# logic_pirate.net
KiCad netlist of a schematic drawn in EAGLE
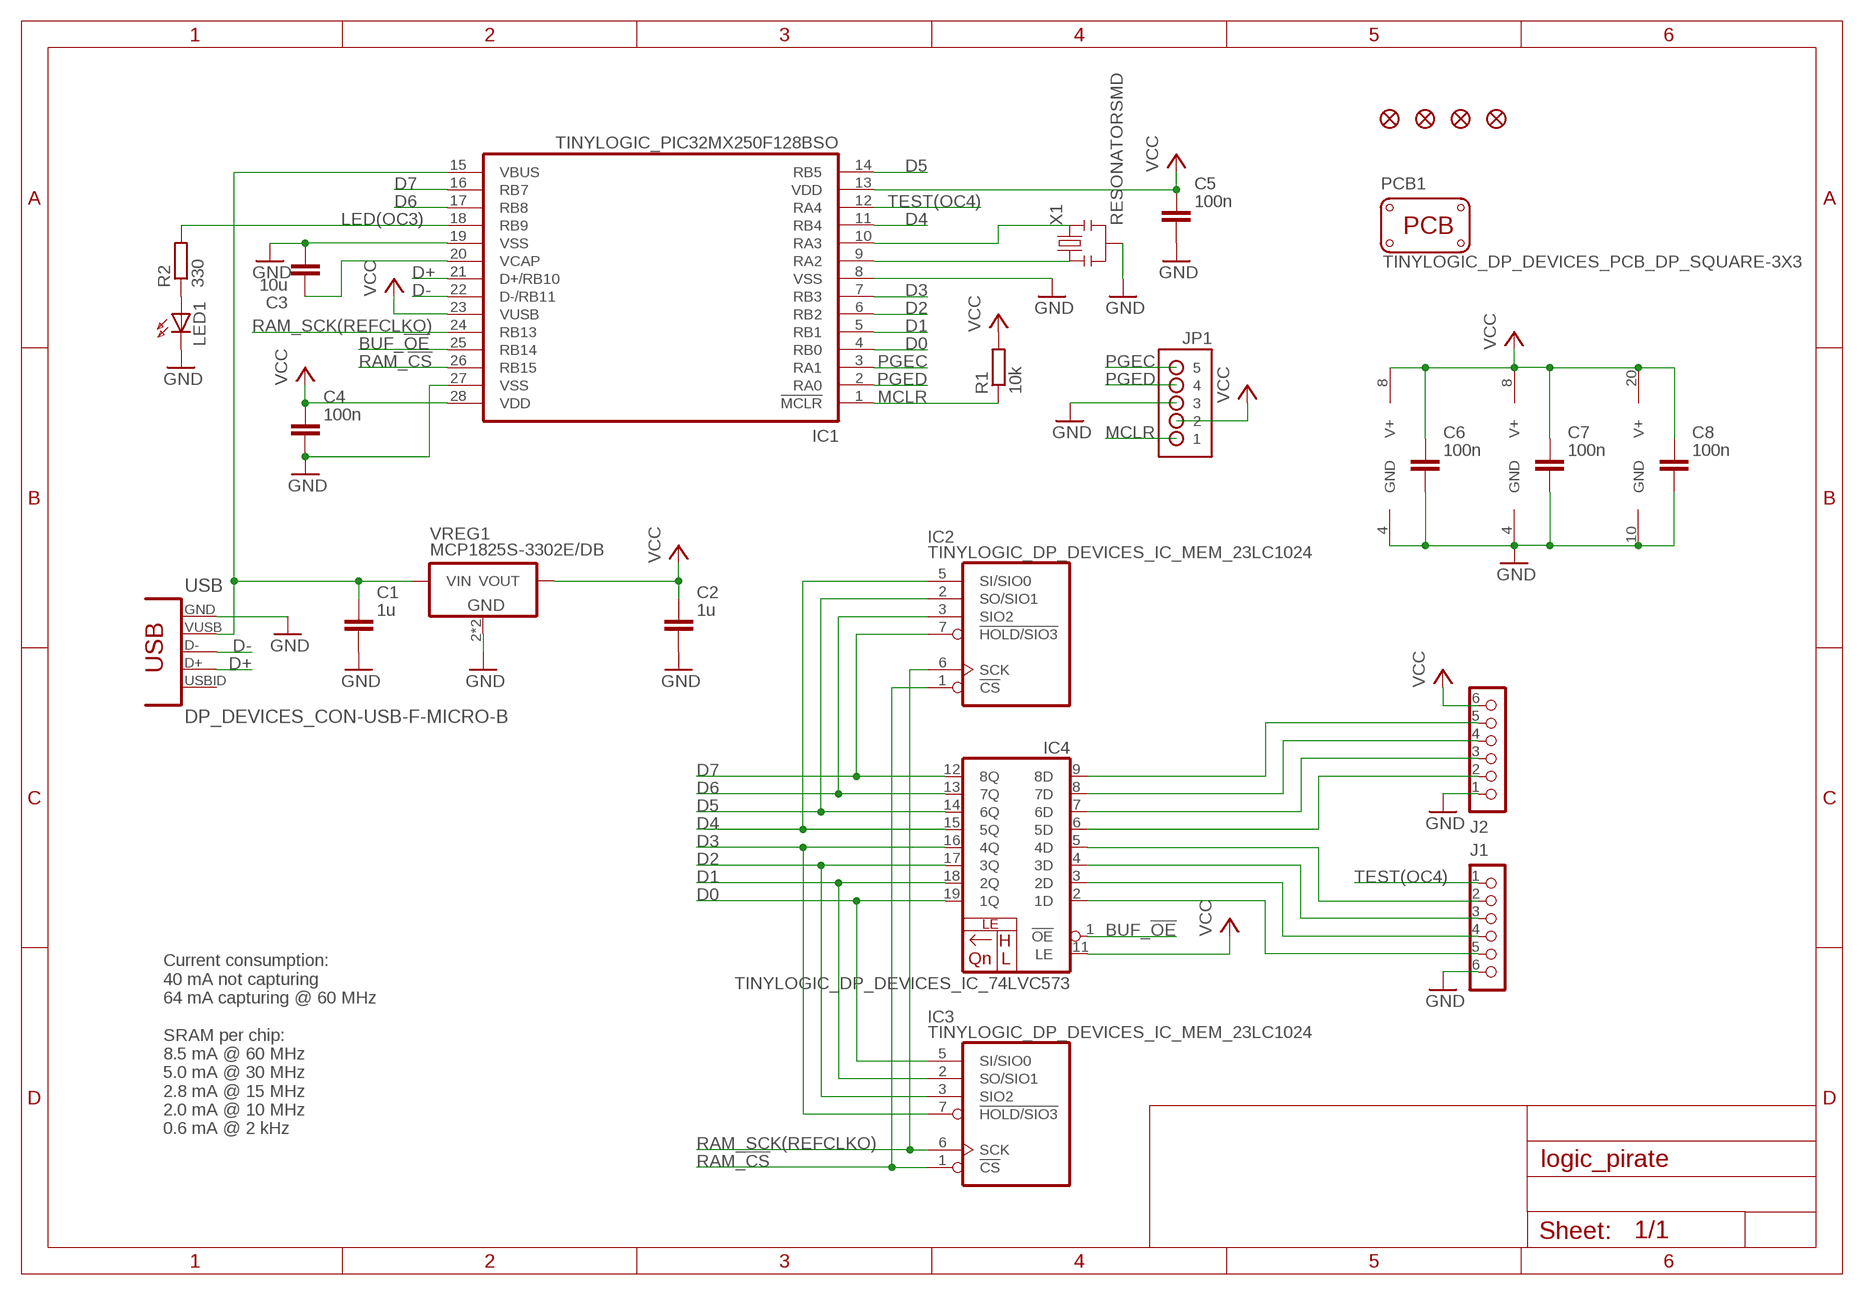
[diagram p0: schematic, sheet 1]

(export (version "E")
  (design (tool "Eeschema 10.0.6"))
  (components
    (comp (ref "C1")
      (value "1u")
      (footprint "eagle-import:DP_DEVICES_C603")
      (libsource (lib "eagle-import") (part "DP_DEVICES_CAPACITOR_NPOL-0603"))
    )
    (comp (ref "C2")
      (value "1u")
      (footprint "eagle-import:DP_DEVICES_C603")
      (libsource (lib "eagle-import") (part "DP_DEVICES_CAPACITOR_NPOL-0603"))
    )
    (comp (ref "C3")
      (value "10u")
      (footprint "eagle-import:C1206")
      (libsource (lib "eagle-import") (part "CAPACITOR_NPOL-1206"))
    )
    (comp (ref "C4")
      (value "100n")
      (footprint "eagle-import:DP_DEVICES_C603")
      (libsource (lib "eagle-import") (part "DP_DEVICES_CAPACITOR_NPOL-0603"))
    )
    (comp (ref "C5")
      (value "100n")
      (footprint "eagle-import:DP_DEVICES_C603")
      (libsource (lib "eagle-import") (part "DP_DEVICES_CAPACITOR_NPOL-0603"))
    )
    (comp (ref "C6")
      (value "100n")
      (footprint "eagle-import:DP_DEVICES_C603")
      (libsource (lib "eagle-import") (part "DP_DEVICES_CAPACITOR_NPOL-0603"))
    )
    (comp (ref "C7")
      (value "100n")
      (footprint "eagle-import:DP_DEVICES_C603")
      (libsource (lib "eagle-import") (part "DP_DEVICES_CAPACITOR_NPOL-0603"))
    )
    (comp (ref "C8")
      (value "100n")
      (footprint "eagle-import:DP_DEVICES_C603")
      (libsource (lib "eagle-import") (part "DP_DEVICES_CAPACITOR_NPOL-0603"))
    )
    (comp (ref "IC1")
      (value "TINYLOGIC_PIC32MX250F128BSO")
      (footprint "eagle-import:TINYLOGIC_DP_DEVICES_SOIC-28W")
      (libsource (lib "eagle-import") (part "TINYLOGIC_PIC32MX250F128BSO"))
    )
    (comp (ref "IC2")
      (value "TINYLOGIC_DP_DEVICES_IC_MEM_23LC1024")
      (footprint "eagle-import:TINYLOGIC_DP_DEVICES_SOIC-8")
      (libsource (lib "eagle-import") (part "TINYLOGIC_DP_DEVICES_IC_MEM_23LC1024"))
    )
    (comp (ref "IC3")
      (value "TINYLOGIC_DP_DEVICES_IC_MEM_23LC1024")
      (footprint "eagle-import:TINYLOGIC_DP_DEVICES_SOIC-8")
      (libsource (lib "eagle-import") (part "TINYLOGIC_DP_DEVICES_IC_MEM_23LC1024"))
    )
    (comp (ref "IC4")
      (value "TINYLOGIC_DP_DEVICES_IC_74LVC573")
      (footprint "eagle-import:TINYLOGIC_DP_DEVICES_SOIC-20")
      (libsource (lib "eagle-import") (part "TINYLOGIC_DP_DEVICES_IC_74LVC573"))
    )
    (comp (ref "J1")
      (value "DP_DEVICES_CON_HEADER_1X06-SMD-RIGHT-ANGLED")
      (footprint "eagle-import:DP_DEVICES_M1X6_MALE_RIGHT_ANGLED_SMD")
      (libsource (lib "eagle-import") (part "DP_DEVICES_CON_HEADER_1X06-SMD-RIGHT-ANGLED"))
    )
    (comp (ref "J2")
      (value "DP_DEVICES_CON_HEADER_1X06-SMD-RIGHT-ANGLED")
      (footprint "eagle-import:DP_DEVICES_M1X6_MALE_RIGHT_ANGLED_SMD")
      (libsource (lib "eagle-import") (part "DP_DEVICES_CON_HEADER_1X06-SMD-RIGHT-ANGLED"))
    )
    (comp (ref "JP1")
      (value "TINYLOGIC_CHIPKIT_UNO32_MECHANICAL_HDR-1X5-OFFSET")
      (footprint "eagle-import:TINYLOGIC_CHIPKIT_UNO32_MECHANICAL_HDR-1X6_OFFSET")
      (libsource (lib "eagle-import") (part "TINYLOGIC_CHIPKIT_UNO32_MECHANICAL_HDR-1X5-OFFSET"))
    )
    (comp (ref "JP2")
      (value "FIDUCIAL1X2")
      (footprint "eagle-import:FIDUCIAL-1X2")
      (libsource (lib "eagle-import") (part "FIDUCIAL1X2"))
    )
    (comp (ref "JP3")
      (value "FIDUCIAL1X2")
      (footprint "eagle-import:FIDUCIAL-1X2")
      (libsource (lib "eagle-import") (part "FIDUCIAL1X2"))
    )
    (comp (ref "JP4")
      (value "FIDUCIAL1X2")
      (footprint "eagle-import:FIDUCIAL-1X2")
      (libsource (lib "eagle-import") (part "FIDUCIAL1X2"))
    )
    (comp (ref "JP5")
      (value "FIDUCIAL1X2")
      (footprint "eagle-import:FIDUCIAL-1X2")
      (libsource (lib "eagle-import") (part "FIDUCIAL1X2"))
    )
    (comp (ref "LED1")
      (value "Status")
      (footprint "eagle-import:CHIPKIT_UNO32_DISCRETE_D0603")
      (libsource (lib "eagle-import") (part "CHIPKIT_UNO32_DISCRETE_LED-S0603"))
    )
    (comp (ref "PCB1")
      (value "TINYLOGIC_DP_DEVICES_PCB_DP_SQUARE-3X3")
      (footprint "eagle-import:TINYLOGIC_DP_DEVICES_DP3030_V1")
      (libsource (lib "eagle-import") (part "TINYLOGIC_DP_DEVICES_PCB_DP_SQUARE-3X3"))
    )
    (comp (ref "R1")
      (value "10k")
      (footprint "eagle-import:DP_DEVICES_R603")
      (libsource (lib "eagle-import") (part "DP_DEVICES_RESISTOR-0603"))
    )
    (comp (ref "R2")
      (value "330")
      (footprint "eagle-import:DP_DEVICES_R603")
      (libsource (lib "eagle-import") (part "DP_DEVICES_RESISTOR-0603"))
    )
    (comp (ref "USB")
      (value "DP_DEVICES_CON-USB-F-MICRO-B")
      (footprint "eagle-import:DP_DEVICES_CONN_USB_MICRO-B")
      (libsource (lib "eagle-import") (part "DP_DEVICES_CON-USB-F-MICRO-B"))
    )
    (comp (ref "VREG1")
      (value "MCP1825S-3302E/DB")
      (footprint "eagle-import:DP_DEVICES_SOT-223")
      (libsource (lib "eagle-import") (part "DP_DEVICES_VREG_3PINS-SOT-223"))
    )
    (comp (ref "X1")
      (value "RESONATORSMD")
      (footprint "eagle-import:RESONATOR-SMD")
      (libsource (lib "eagle-import") (part "RESONATORSMD"))
    )
  )
  (nets
    (net (code "1") (name "/BUF_~{OE}") (class "Default")
      (node (ref "IC1") (pin "25") (pinfunction "RB14_25") (pintype "bidirectional"))
      (node (ref "IC4") (pin "1") (pinfunction "~{OE}_1") (pintype "input"))
    )
    (net (code "2") (name "/D+") (class "Default")
      (node (ref "IC1") (pin "21") (pinfunction "D+/RB10_21") (pintype "bidirectional"))
      (node (ref "USB") (pin "P3") (pinfunction "D+_P3") (pintype "bidirectional"))
    )
    (net (code "3") (name "/D-") (class "Default")
      (node (ref "IC1") (pin "22") (pinfunction "D-/RB11_22") (pintype "bidirectional"))
      (node (ref "USB") (pin "P2") (pinfunction "D-_P2") (pintype "bidirectional"))
    )
    (net (code "4") (name "/D0") (class "Default")
      (node (ref "IC1") (pin "4") (pinfunction "RB0_4") (pintype "bidirectional"))
      (node (ref "IC3") (pin "5") (pinfunction "SI/SIO0_5") (pintype "bidirectional"))
      (node (ref "IC4") (pin "19") (pinfunction "1Q_19") (pintype "bidirectional"))
    )
    (net (code "5") (name "/D1") (class "Default")
      (node (ref "IC1") (pin "5") (pinfunction "RB1_5") (pintype "bidirectional"))
      (node (ref "IC3") (pin "2") (pinfunction "SO/SIO1_2") (pintype "bidirectional"))
      (node (ref "IC4") (pin "18") (pinfunction "2Q_18") (pintype "bidirectional"))
    )
    (net (code "6") (name "/D2") (class "Default")
      (node (ref "IC1") (pin "6") (pinfunction "RB2_6") (pintype "bidirectional"))
      (node (ref "IC3") (pin "3") (pinfunction "SIO2_3") (pintype "bidirectional"))
      (node (ref "IC4") (pin "17") (pinfunction "3Q_17") (pintype "bidirectional"))
    )
    (net (code "7") (name "/D3") (class "Default")
      (node (ref "IC1") (pin "7") (pinfunction "RB3_7") (pintype "bidirectional"))
      (node (ref "IC3") (pin "7") (pinfunction "~{HOLD/SIO3}_7") (pintype "input"))
      (node (ref "IC4") (pin "16") (pinfunction "4Q_16") (pintype "bidirectional"))
    )
    (net (code "8") (name "/D4") (class "Default")
      (node (ref "IC1") (pin "11") (pinfunction "RB4_11") (pintype "bidirectional"))
      (node (ref "IC2") (pin "5") (pinfunction "SI/SIO0_5") (pintype "bidirectional"))
      (node (ref "IC4") (pin "15") (pinfunction "5Q_15") (pintype "bidirectional"))
    )
    (net (code "9") (name "/D5") (class "Default")
      (node (ref "IC1") (pin "14") (pinfunction "RB5_14") (pintype "bidirectional"))
      (node (ref "IC2") (pin "2") (pinfunction "SO/SIO1_2") (pintype "bidirectional"))
      (node (ref "IC4") (pin "14") (pinfunction "6Q_14") (pintype "bidirectional"))
    )
    (net (code "10") (name "/D6") (class "Default")
      (node (ref "IC1") (pin "17") (pinfunction "RB8_17") (pintype "bidirectional"))
      (node (ref "IC2") (pin "3") (pinfunction "SIO2_3") (pintype "bidirectional"))
      (node (ref "IC4") (pin "13") (pinfunction "7Q_13") (pintype "bidirectional"))
    )
    (net (code "11") (name "/D7") (class "Default")
      (node (ref "IC1") (pin "16") (pinfunction "RB7_16") (pintype "bidirectional"))
      (node (ref "IC2") (pin "7") (pinfunction "~{HOLD/SIO3}_7") (pintype "input"))
      (node (ref "IC4") (pin "12") (pinfunction "8Q_12") (pintype "bidirectional"))
    )
    (net (code "12") (name "/LED(OC3)") (class "Default")
      (node (ref "IC1") (pin "18") (pinfunction "RB9_18") (pintype "bidirectional"))
      (node (ref "R2") (pin "2") (pinfunction "2_2") (pintype "passive"))
    )
    (net (code "13") (name "/MCLR") (class "Default")
      (node (ref "IC1") (pin "1") (pinfunction "~{MCLR}_1") (pintype "bidirectional"))
      (node (ref "JP1") (pin "1") (pinfunction "1_1") (pintype "passive"))
      (node (ref "R1") (pin "1") (pinfunction "1_1") (pintype "passive"))
    )
    (net (code "14") (name "/PGEC") (class "Default")
      (node (ref "IC1") (pin "3") (pinfunction "RA1_3") (pintype "bidirectional"))
      (node (ref "JP1") (pin "5") (pinfunction "5_5") (pintype "passive"))
    )
    (net (code "15") (name "/PGED") (class "Default")
      (node (ref "IC1") (pin "2") (pinfunction "RA0_2") (pintype "bidirectional"))
      (node (ref "JP1") (pin "4") (pinfunction "4_4") (pintype "passive"))
    )
    (net (code "16") (name "/RAM_SCK(REFCLKO)") (class "Default")
      (node (ref "IC1") (pin "24") (pinfunction "RB13_24") (pintype "bidirectional"))
      (node (ref "IC2") (pin "6") (pinfunction "SCK_6") (pintype "input"))
      (node (ref "IC3") (pin "6") (pinfunction "SCK_6") (pintype "input"))
    )
    (net (code "17") (name "/RAM_~{CS}") (class "Default")
      (node (ref "IC1") (pin "26") (pinfunction "RB15_26") (pintype "bidirectional"))
      (node (ref "IC2") (pin "1") (pinfunction "~{CS}_1") (pintype "input"))
      (node (ref "IC3") (pin "1") (pinfunction "~{CS}_1") (pintype "input"))
    )
    (net (code "18") (name "/TEST(OC4)") (class "Default")
      (node (ref "IC1") (pin "12") (pinfunction "RA4_12") (pintype "bidirectional"))
      (node (ref "J1") (pin "1") (pinfunction "1_1") (pintype "bidirectional"))
    )
    (net (code "19") (name "GND") (class "Default")
      (node (ref "C1") (pin "2") (pinfunction "2_2") (pintype "passive"))
      (node (ref "C2") (pin "2") (pinfunction "2_2") (pintype "passive"))
      (node (ref "C3") (pin "2") (pinfunction "2_2") (pintype "passive"))
      (node (ref "C4") (pin "2") (pinfunction "2_2") (pintype "passive"))
      (node (ref "C5") (pin "2") (pinfunction "2_2") (pintype "passive"))
      (node (ref "C6") (pin "2") (pinfunction "2_2") (pintype "passive"))
      (node (ref "C7") (pin "2") (pinfunction "2_2") (pintype "passive"))
      (node (ref "C8") (pin "2") (pinfunction "2_2") (pintype "passive"))
      (node (ref "IC1") (pin "19") (pinfunction "VSS_19") (pintype "passive"))
      (node (ref "IC1") (pin "27") (pinfunction "VSS_27") (pintype "power_in"))
      (node (ref "IC1") (pin "8") (pinfunction "VSS_8") (pintype "power_in"))
      (node (ref "IC2") (pin "4") (pinfunction "GND_4") (pintype "power_in"))
      (node (ref "IC3") (pin "4") (pinfunction "GND_4") (pintype "power_in"))
      (node (ref "IC4") (pin "10") (pinfunction "GND_10") (pintype "power_in"))
      (node (ref "J1") (pin "6") (pinfunction "6_6") (pintype "passive"))
      (node (ref "J2") (pin "1") (pinfunction "1_1") (pintype "bidirectional"))
      (node (ref "JP1") (pin "3") (pinfunction "3_3") (pintype "passive"))
      (node (ref "LED1") (pin "C") (pinfunction "C_C") (pintype "passive"))
      (node (ref "USB") (pin "P5") (pinfunction "GND_P5") (pintype "bidirectional"))
      (node (ref "VREG1") (pin "2") (pinfunction "GND_2") (pintype "bidirectional"))
      (node (ref "VREG1") (pin "4") (pinfunction "GND_4") (pintype "bidirectional"))
      (node (ref "X1") (pin "2") (pinfunction "2_2") (pintype "passive"))
    )
    (net (code "20") (name "Net-(IC1-RA2)") (class "Default")
      (node (ref "IC1") (pin "9") (pinfunction "RA2_9") (pintype "bidirectional"))
      (node (ref "X1") (pin "1") (pinfunction "1_1") (pintype "passive"))
    )
    (net (code "21") (name "Net-(IC1-RA3)") (class "Default")
      (node (ref "IC1") (pin "10") (pinfunction "RA3_10") (pintype "bidirectional"))
      (node (ref "X1") (pin "3") (pinfunction "3_3") (pintype "passive"))
    )
    (net (code "22") (name "Net-(IC1-VBUS)") (class "Default")
      (node (ref "C1") (pin "1") (pinfunction "1_1") (pintype "passive"))
      (node (ref "IC1") (pin "15") (pinfunction "VBUS_15") (pintype "power_in"))
      (node (ref "USB") (pin "P1") (pinfunction "VUSB_P1") (pintype "bidirectional"))
      (node (ref "VREG1") (pin "1") (pinfunction "VIN_1") (pintype "bidirectional"))
    )
    (net (code "23") (name "Net-(IC1-VCAP)") (class "Default")
      (node (ref "C3") (pin "1") (pinfunction "1_1") (pintype "passive"))
      (node (ref "IC1") (pin "20") (pinfunction "VCAP_20") (pintype "power_in"))
    )
    (net (code "24") (name "Net-(IC4A-1D)") (class "Default")
      (node (ref "IC4") (pin "2") (pinfunction "1D_2") (pintype "bidirectional"))
      (node (ref "J1") (pin "5") (pinfunction "5_5") (pintype "passive"))
    )
    (net (code "25") (name "Net-(IC4A-2D)") (class "Default")
      (node (ref "IC4") (pin "3") (pinfunction "2D_3") (pintype "bidirectional"))
      (node (ref "J1") (pin "4") (pinfunction "4_4") (pintype "passive"))
    )
    (net (code "26") (name "Net-(IC4A-3D)") (class "Default")
      (node (ref "IC4") (pin "4") (pinfunction "3D_4") (pintype "bidirectional"))
      (node (ref "J1") (pin "3") (pinfunction "3_3") (pintype "passive"))
    )
    (net (code "27") (name "Net-(IC4A-4D)") (class "Default")
      (node (ref "IC4") (pin "5") (pinfunction "4D_5") (pintype "bidirectional"))
      (node (ref "J1") (pin "2") (pinfunction "2_2") (pintype "bidirectional"))
    )
    (net (code "28") (name "Net-(IC4A-5D)") (class "Default")
      (node (ref "IC4") (pin "6") (pinfunction "5D_6") (pintype "bidirectional"))
      (node (ref "J2") (pin "2") (pinfunction "2_2") (pintype "bidirectional"))
    )
    (net (code "29") (name "Net-(IC4A-6D)") (class "Default")
      (node (ref "IC4") (pin "7") (pinfunction "6D_7") (pintype "bidirectional"))
      (node (ref "J2") (pin "3") (pinfunction "3_3") (pintype "passive"))
    )
    (net (code "30") (name "Net-(IC4A-7D)") (class "Default")
      (node (ref "IC4") (pin "8") (pinfunction "7D_8") (pintype "bidirectional"))
      (node (ref "J2") (pin "4") (pinfunction "4_4") (pintype "passive"))
    )
    (net (code "31") (name "Net-(IC4A-8D)") (class "Default")
      (node (ref "IC4") (pin "9") (pinfunction "8D_9") (pintype "bidirectional"))
      (node (ref "J2") (pin "5") (pinfunction "5_5") (pintype "passive"))
    )
    (net (code "32") (name "Net-(LED1-PadA)") (class "Default")
      (node (ref "LED1") (pin "A") (pinfunction "A_A") (pintype "passive"))
      (node (ref "R2") (pin "1") (pinfunction "1_1") (pintype "passive"))
    )
    (net (code "33") (name "VCC") (class "Default")
      (node (ref "C2") (pin "1") (pinfunction "1_1") (pintype "passive"))
      (node (ref "C4") (pin "1") (pinfunction "1_1") (pintype "passive"))
      (node (ref "C5") (pin "1") (pinfunction "1_1") (pintype "passive"))
      (node (ref "C6") (pin "1") (pinfunction "1_1") (pintype "passive"))
      (node (ref "C7") (pin "1") (pinfunction "1_1") (pintype "passive"))
      (node (ref "C8") (pin "1") (pinfunction "1_1") (pintype "passive"))
      (node (ref "IC1") (pin "13") (pinfunction "VDD_13") (pintype "power_in"))
      (node (ref "IC1") (pin "23") (pinfunction "VUSB_23") (pintype "bidirectional"))
      (node (ref "IC1") (pin "28") (pinfunction "VDD_28") (pintype "power_in"))
      (node (ref "IC2") (pin "8") (pinfunction "V+_8") (pintype "power_in"))
      (node (ref "IC3") (pin "8") (pinfunction "V+_8") (pintype "power_in"))
      (node (ref "IC4") (pin "11") (pinfunction "LE_11") (pintype "input"))
      (node (ref "IC4") (pin "20") (pinfunction "V+_20") (pintype "power_in"))
      (node (ref "J2") (pin "6") (pinfunction "6_6") (pintype "passive"))
      (node (ref "JP1") (pin "2") (pinfunction "2_2") (pintype "passive"))
      (node (ref "R1") (pin "2") (pinfunction "2_2") (pintype "passive"))
      (node (ref "VREG1") (pin "3") (pinfunction "VOUT_3") (pintype "bidirectional"))
    )
    (net (code "34") (name "unconnected-(USBB-USBID-PadP4)") (class "Default")
      (node (ref "USB") (pin "P4") (pinfunction "USBID_P4") (pintype "bidirectional"))
    )
  )
)
